# Arduino_MEGA_2560-Rev3.net
KiCad netlist of a schematic drawn in EAGLE
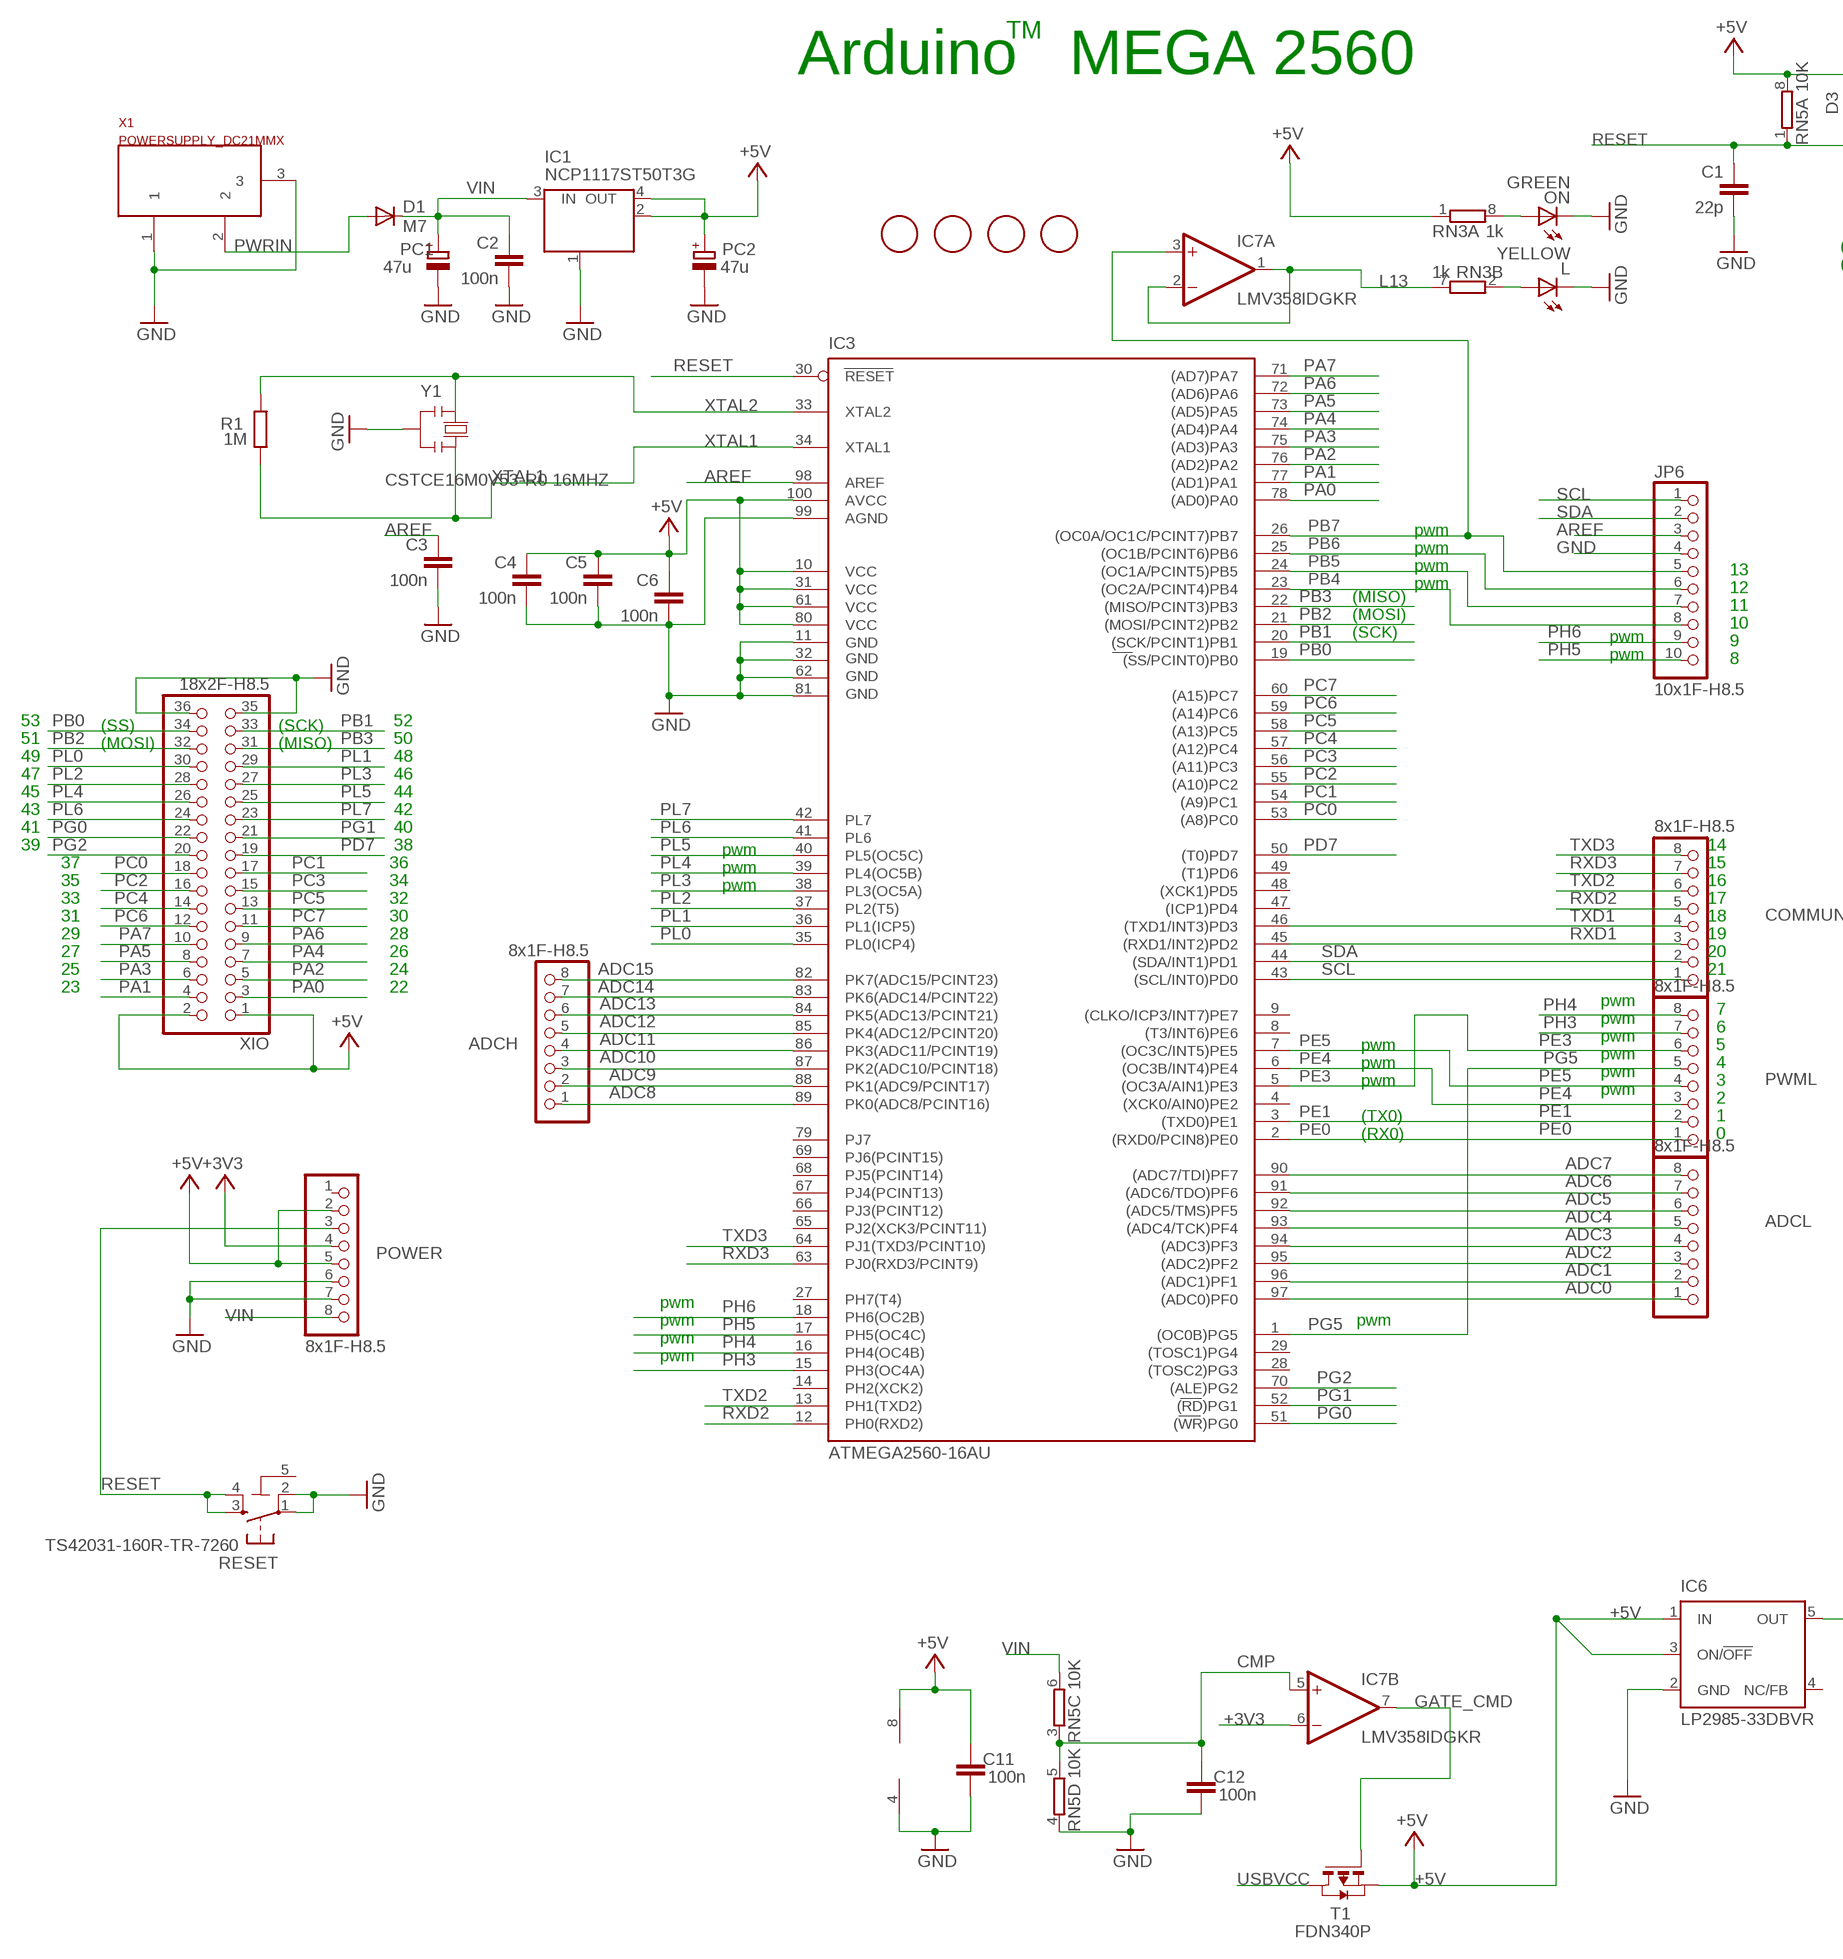
[diagram p0: schematic, sheet 1, part 1 of 2]
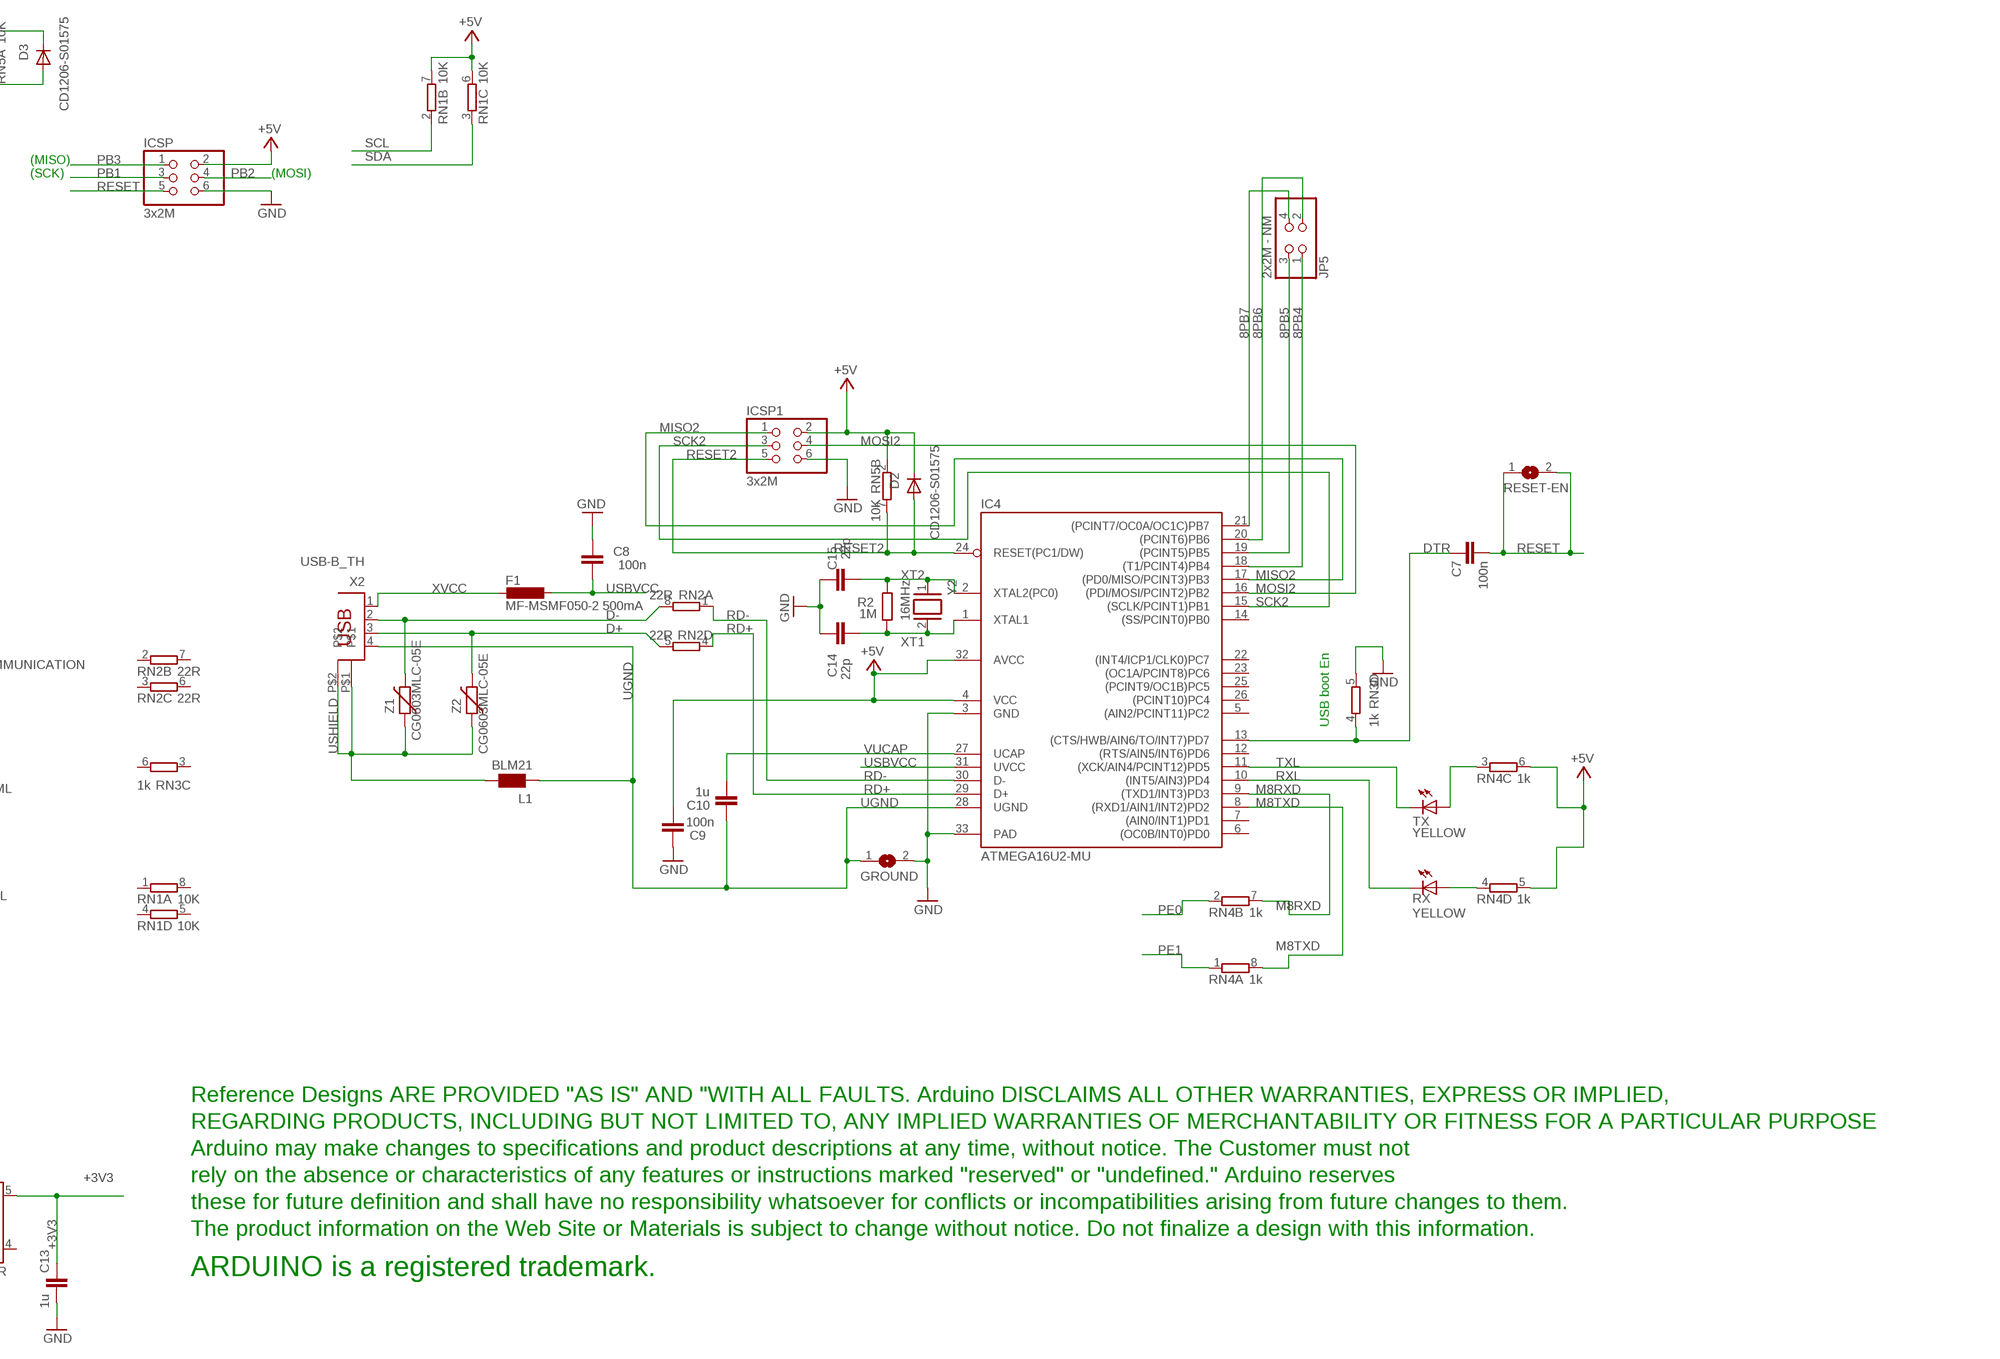
[diagram p1: schematic, sheet 1, part 2 of 2]

(export (version "E")
  (design (tool "Eeschema 10.0.6"))
  (components
    (comp (ref "ADCH")
      (value "8x1F-H8.5")
      (footprint "eagle-import:1X08")
      (libsource (lib "eagle-import") (part "PINHD-1X8"))
    )
    (comp (ref "ADCL")
      (value "8x1F-H8.5")
      (footprint "eagle-import:1X08")
      (libsource (lib "eagle-import") (part "PINHD-1X8"))
    )
    (comp (ref "C1")
      (value "22p")
      (footprint "eagle-import:C0603-ROUND")
      (libsource (lib "eagle-import") (part "C-EU0603-RND"))
    )
    (comp (ref "C2")
      (value "100n")
      (footprint "eagle-import:C0603-ROUND")
      (libsource (lib "eagle-import") (part "C-EU0603-RND"))
    )
    (comp (ref "C3")
      (value "100n")
      (footprint "eagle-import:C0603-ROUND")
      (libsource (lib "eagle-import") (part "C-EU0603-RND"))
    )
    (comp (ref "C4")
      (value "100n")
      (footprint "eagle-import:C0603-ROUND")
      (libsource (lib "eagle-import") (part "C-EU0603-RND"))
    )
    (comp (ref "C5")
      (value "100n")
      (footprint "eagle-import:C0603-ROUND")
      (libsource (lib "eagle-import") (part "C-EU0603-RND"))
    )
    (comp (ref "C6")
      (value "100n")
      (footprint "eagle-import:C0603-ROUND")
      (libsource (lib "eagle-import") (part "C-EU0603-RND"))
    )
    (comp (ref "C7")
      (value "100n")
      (footprint "eagle-import:C0603-ROUND")
      (libsource (lib "eagle-import") (part "C-EU0603-RND"))
    )
    (comp (ref "C8")
      (value "100n")
      (footprint "eagle-import:C0603-ROUND")
      (libsource (lib "eagle-import") (part "C-EU0603-RND"))
    )
    (comp (ref "C9")
      (value "100n")
      (footprint "eagle-import:C0603-ROUND")
      (libsource (lib "eagle-import") (part "C-EU0603-RND"))
    )
    (comp (ref "C10")
      (value "1u")
      (footprint "eagle-import:C0603-ROUND")
      (libsource (lib "eagle-import") (part "C-EU0603-RND"))
    )
    (comp (ref "C11")
      (value "100n")
      (footprint "eagle-import:C0603-ROUND")
      (libsource (lib "eagle-import") (part "C-EU0603-RND"))
    )
    (comp (ref "C12")
      (value "100n")
      (footprint "eagle-import:C0603-ROUND")
      (libsource (lib "eagle-import") (part "C-EU0603-RND"))
    )
    (comp (ref "C13")
      (value "1u")
      (footprint "eagle-import:C0603-ROUND")
      (libsource (lib "eagle-import") (part "C-EU0603-RND"))
    )
    (comp (ref "C14")
      (value "22p")
      (footprint "eagle-import:C0603-ROUND")
      (libsource (lib "eagle-import") (part "C-EU0603-RND"))
    )
    (comp (ref "C15")
      (value "22p")
      (footprint "eagle-import:C0603-ROUND")
      (libsource (lib "eagle-import") (part "C-EU0603-RND"))
    )
    (comp (ref "COMMUNICATION")
      (value "8x1F-H8.5")
      (footprint "eagle-import:1X08")
      (libsource (lib "eagle-import") (part "PINHD-1X8"))
    )
    (comp (ref "D1")
      (value "M7")
      (footprint "eagle-import:SMB")
      (libsource (lib "eagle-import") (part "DIODE-SMB"))
    )
    (comp (ref "D2")
      (value "CD1206-S01575")
      (footprint "eagle-import:MINIMELF")
      (libsource (lib "eagle-import") (part "DIODE-MINIMELF"))
    )
    (comp (ref "D3")
      (value "CD1206-S01575")
      (footprint "eagle-import:MINIMELF")
      (libsource (lib "eagle-import") (part "DIODE-MINIMELF"))
    )
    (comp (ref "F1")
      (value "MF-MSMF050-2 500mA")
      (footprint "eagle-import:L1812")
      (libsource (lib "eagle-import") (part "L-EUL1812"))
    )
    (comp (ref "FD1")
      (value "FIDUCIALMOUNT")
      (footprint "eagle-import:FIDUCIA-MOUNT")
      (libsource (lib "eagle-import") (part "FIDUCIALMOUNT"))
    )
    (comp (ref "FD2")
      (value "FIDUCIALMOUNT")
      (footprint "eagle-import:FIDUCIA-MOUNT")
      (libsource (lib "eagle-import") (part "FIDUCIALMOUNT"))
    )
    (comp (ref "FD3")
      (value "FIDUCIALMOUNT")
      (footprint "eagle-import:FIDUCIA-MOUNT")
      (libsource (lib "eagle-import") (part "FIDUCIALMOUNT"))
    )
    (comp (ref "FD4")
      (value "FIDUCIALMOUNT")
      (footprint "eagle-import:FIDUCIA-MOUNT")
      (libsource (lib "eagle-import") (part "FIDUCIALMOUNT"))
    )
    (comp (ref "GROUND")
      (value "SJ")
      (footprint "eagle-import:SJ")
      (libsource (lib "eagle-import") (part "SJ"))
    )
    (comp (ref "IC1")
      (value "NCP1117ST50T3G")
      (footprint "eagle-import:SOT223")
      (libsource (lib "eagle-import") (part "MC33269ST-3.3T3"))
    )
    (comp (ref "IC3")
      (value "ATMEGA2560-16AU")
      (footprint "eagle-import:TQFP100")
      (libsource (lib "eagle-import") (part "ATMEGA2560AU2560-16"))
    )
    (comp (ref "IC4")
      (value "ATMEGA16U2-MU")
      (footprint "eagle-import:MLF32")
      (libsource (lib "eagle-import") (part "ATMEGA16U2-MU"))
    )
    (comp (ref "IC6")
      (value "LP2985-33DBVR")
      (footprint "eagle-import:SOT23-DBV")
      (libsource (lib "eagle-import") (part "LP2985-XXDBVR33"))
    )
    (comp (ref "IC7")
      (value "LMV358IDGKR")
      (footprint "eagle-import:MSOP08")
      (libsource (lib "eagle-import") (part "LMV358?MMX"))
    )
    (comp (ref "ICSP")
      (value "3x2M")
      (footprint "eagle-import:2X03")
      (libsource (lib "eagle-import") (part "PINHD-2X3"))
    )
    (comp (ref "ICSP1")
      (value "3x2M")
      (footprint "eagle-import:2X03")
      (libsource (lib "eagle-import") (part "PINHD-2X3"))
    )
    (comp (ref "JP5")
      (value "2x2M - NM")
      (footprint "eagle-import:2X02")
      (libsource (lib "eagle-import") (part "PINHD-2X2"))
    )
    (comp (ref "JP6")
      (value "10x1F-H8.5")
      (footprint "eagle-import:1X10")
      (libsource (lib "eagle-import") (part "PINHD-1X10_ARD"))
    )
    (comp (ref "L")
      (value "YELLOW")
      (footprint "eagle-import:CHIP-LED0805")
      (libsource (lib "eagle-import") (part "LEDCHIP-LED0805"))
    )
    (comp (ref "L1")
      (value "BLM21")
      (footprint "eagle-import:0805")
      (libsource (lib "eagle-import") (part "WE-CBF_0805"))
    )
    (comp (ref "ON")
      (value "GREEN")
      (footprint "eagle-import:CHIP-LED0805")
      (libsource (lib "eagle-import") (part "LEDCHIP-LED0805"))
    )
    (comp (ref "PC1")
      (value "47u")
      (footprint "eagle-import:PANASONIC_D")
      (libsource (lib "eagle-import") (part "CPOL-EUD"))
    )
    (comp (ref "PC2")
      (value "47u")
      (footprint "eagle-import:PANASONIC_D")
      (libsource (lib "eagle-import") (part "CPOL-EUD"))
    )
    (comp (ref "POWER")
      (value "8x1F-H8.5")
      (footprint "eagle-import:1X08")
      (libsource (lib "eagle-import") (part "PINHD-1X8"))
    )
    (comp (ref "PWML")
      (value "8x1F-H8.5")
      (footprint "eagle-import:1X08")
      (libsource (lib "eagle-import") (part "PINHD-1X8"))
    )
    (comp (ref "R1")
      (value "1M")
      (footprint "eagle-import:R0603-ROUND")
      (libsource (lib "eagle-import") (part "R-EU_R0603"))
    )
    (comp (ref "R2")
      (value "1M")
      (footprint "eagle-import:R0603-ROUND")
      (libsource (lib "eagle-import") (part "R-EU_R0603"))
    )
    (comp (ref "RESET")
      (value "TS42031-160R-TR-7260")
      (footprint "eagle-import:TS42")
      (libsource (lib "eagle-import") (part "TS42"))
    )
    (comp (ref "RESET-EN")
      (value "SJ")
      (footprint "eagle-import:SJ")
      (libsource (lib "eagle-import") (part "SJ"))
    )
    (comp (ref "RN1")
      (value "10K")
      (footprint "eagle-import:CAT16")
      (libsource (lib "eagle-import") (part "4R-NCAT16"))
    )
    (comp (ref "RN2")
      (value "22R")
      (footprint "eagle-import:CAY16")
      (libsource (lib "eagle-import") (part "4R-NCAY16"))
    )
    (comp (ref "RN3")
      (value "1k")
      (footprint "eagle-import:CAY16")
      (libsource (lib "eagle-import") (part "4R-NCAY16"))
    )
    (comp (ref "RN4")
      (value "1k")
      (footprint "eagle-import:CAY16")
      (libsource (lib "eagle-import") (part "4R-NCAY16"))
    )
    (comp (ref "RN5")
      (value "10K")
      (footprint "eagle-import:CAT16")
      (libsource (lib "eagle-import") (part "4R-NCAT16"))
    )
    (comp (ref "RX")
      (value "YELLOW")
      (footprint "eagle-import:CHIP-LED0805")
      (libsource (lib "eagle-import") (part "LEDCHIP-LED0805"))
    )
    (comp (ref "T1")
      (value "FDN340P")
      (footprint "eagle-import:SOT-23")
      (libsource (lib "eagle-import") (part "PMOSSOT23"))
    )
    (comp (ref "TX")
      (value "YELLOW")
      (footprint "eagle-import:CHIP-LED0805")
      (libsource (lib "eagle-import") (part "LEDCHIP-LED0805"))
    )
    (comp (ref "U$1")
      (value "DISCLAIMER")
      (footprint "eagle-import:DISCLAIMER")
      (libsource (lib "eagle-import") (part "DISCLAIMER"))
    )
    (comp (ref "X1")
      (value "POWERSUPPLY_DC21MMX")
      (footprint "eagle-import:POWERSUPPLY_DC-21MM")
      (libsource (lib "eagle-import") (part "POWERSUPPLY_DC21MMX"))
    )
    (comp (ref "X2")
      (value "USB-B_TH")
      (footprint "eagle-import:PN61729")
      (libsource (lib "eagle-import") (part "PN61729"))
    )
    (comp (ref "XIO")
      (value "18x2F-H8.5")
      (footprint "eagle-import:2X18")
      (libsource (lib "eagle-import") (part "PINHD-2X18"))
    )
    (comp (ref "Y1")
      (value "CSTCE16M0V53-R0 16MHZ")
      (footprint "eagle-import:RESONATOR")
      (libsource (lib "eagle-import") (part "RESONATORMU"))
    )
    (comp (ref "Y2")
      (value "16MHz")
      (footprint "eagle-import:QS")
      (libsource (lib "eagle-import") (part "XTAL/S"))
    )
    (comp (ref "Z1")
      (value "CG0603MLC-05E")
      (footprint "eagle-import:CT_CN0603")
      (libsource (lib "eagle-import") (part "VARISTORCN0603"))
    )
    (comp (ref "Z2")
      (value "CG0603MLC-05E")
      (footprint "eagle-import:CT_CN0603")
      (libsource (lib "eagle-import") (part "VARISTORCN0603"))
    )
  )
  (nets
    (net (code "1") (name "+3V3") (class "Default")
      (node (ref "C13") (pin "2") (pinfunction "2_2") (pintype "passive"))
      (node (ref "IC6") (pin "5") (pinfunction "OUT_5") (pintype "passive"))
      (node (ref "IC7") (pin "6") (pinfunction "-IN_6") (pintype "input"))
      (node (ref "POWER") (pin "4") (pinfunction "4_4") (pintype "passive"))
    )
    (net (code "2") (name "+5V") (class "Default")
      (node (ref "C11") (pin "2") (pinfunction "2_2") (pintype "passive"))
      (node (ref "C4") (pin "1") (pinfunction "1_1") (pintype "passive"))
      (node (ref "C5") (pin "1") (pinfunction "1_1") (pintype "passive"))
      (node (ref "C6") (pin "1") (pinfunction "1_1") (pintype "passive"))
      (node (ref "C9") (pin "1") (pinfunction "1_1") (pintype "passive"))
      (node (ref "D2") (pin "C") (pinfunction "C_C") (pintype "passive"))
      (node (ref "D3") (pin "C") (pinfunction "C_C") (pintype "passive"))
      (node (ref "IC1") (pin "2") (pinfunction "OUT_2") (pintype "passive"))
      (node (ref "IC1") (pin "4") (pinfunction "OUT_4") (pintype "passive"))
      (node (ref "IC3") (pin "10") (pinfunction "VCC_10") (pintype "power_in"))
      (node (ref "IC3") (pin "100") (pinfunction "AVCC_100") (pintype "power_in"))
      (node (ref "IC3") (pin "31") (pinfunction "VCC1_31") (pintype "power_in"))
      (node (ref "IC3") (pin "61") (pinfunction "VCC2_61") (pintype "power_in"))
      (node (ref "IC3") (pin "80") (pinfunction "VCC3_80") (pintype "power_in"))
      (node (ref "IC4") (pin "32") (pinfunction "AVCC_32") (pintype "power_in"))
      (node (ref "IC4") (pin "4") (pinfunction "VCC_4") (pintype "power_in"))
      (node (ref "IC6") (pin "1") (pinfunction "IN_1") (pintype "input"))
      (node (ref "IC6") (pin "3") (pinfunction "ON/~{OFF}_3") (pintype "input"))
      (node (ref "IC7") (pin "8") (pinfunction "V+_8") (pintype "power_in"))
      (node (ref "ICSP") (pin "2") (pinfunction "2_2") (pintype "passive"))
      (node (ref "ICSP1") (pin "2") (pinfunction "2_2") (pintype "passive"))
      (node (ref "PC2") (pin "+") (pinfunction "+_+") (pintype "passive"))
      (node (ref "POWER") (pin "2") (pinfunction "2_2") (pintype "passive"))
      (node (ref "POWER") (pin "5") (pinfunction "5_5") (pintype "passive"))
      (node (ref "RN1") (pin "6") (pinfunction "2_6") (pintype "passive"))
      (node (ref "RN1") (pin "7") (pinfunction "2_7") (pintype "passive"))
      (node (ref "RN3") (pin "1") (pinfunction "1_1") (pintype "passive"))
      (node (ref "RN4") (pin "5") (pinfunction "2_5") (pintype "passive"))
      (node (ref "RN4") (pin "6") (pinfunction "2_6") (pintype "passive"))
      (node (ref "RN5") (pin "2") (pinfunction "1_2") (pintype "passive"))
      (node (ref "RN5") (pin "8") (pinfunction "2_8") (pintype "passive"))
      (node (ref "T1") (pin "2") (pinfunction "S_2") (pintype "passive"))
      (node (ref "XIO") (pin "1") (pinfunction "1_1") (pintype "passive"))
      (node (ref "XIO") (pin "2") (pinfunction "2_2") (pintype "passive"))
    )
    (net (code "3") (name "/5-GND") (class "Default")
      (node (ref "RESET") (pin "5") (pinfunction "5-GND_5") (pintype "power_in"))
    )
    (net (code "4") (name "/8PB4") (class "Default")
      (node (ref "IC4") (pin "18") (pinfunction "(T1/PCINT4)PB4_18") (pintype "bidirectional"))
      (node (ref "JP5") (pin "1") (pinfunction "1_1") (pintype "passive"))
    )
    (net (code "5") (name "/8PB5") (class "Default")
      (node (ref "IC4") (pin "19") (pinfunction "(PCINT5)PB5_19") (pintype "bidirectional"))
      (node (ref "JP5") (pin "3") (pinfunction "3_3") (pintype "passive"))
    )
    (net (code "6") (name "/8PB6") (class "Default")
      (node (ref "IC4") (pin "20") (pinfunction "(PCINT6)PB6_20") (pintype "bidirectional"))
      (node (ref "JP5") (pin "2") (pinfunction "2_2") (pintype "passive"))
    )
    (net (code "7") (name "/8PB7") (class "Default")
      (node (ref "IC4") (pin "21") (pinfunction "(PCINT7/OC0A/OC1C)PB7_21") (pintype "bidirectional"))
      (node (ref "JP5") (pin "4") (pinfunction "4_4") (pintype "passive"))
    )
    (net (code "8") (name "/ADC0") (class "Default")
      (node (ref "ADCL") (pin "1") (pinfunction "1_1") (pintype "passive"))
      (node (ref "IC3") (pin "97") (pinfunction "(ADC0)PF0_97") (pintype "bidirectional"))
    )
    (net (code "9") (name "/ADC1") (class "Default")
      (node (ref "ADCL") (pin "2") (pinfunction "2_2") (pintype "passive"))
      (node (ref "IC3") (pin "96") (pinfunction "(ADC1)PF1_96") (pintype "bidirectional"))
    )
    (net (code "10") (name "/ADC2") (class "Default")
      (node (ref "ADCL") (pin "3") (pinfunction "3_3") (pintype "passive"))
      (node (ref "IC3") (pin "95") (pinfunction "(ADC2)PF2_95") (pintype "bidirectional"))
    )
    (net (code "11") (name "/ADC3") (class "Default")
      (node (ref "ADCL") (pin "4") (pinfunction "4_4") (pintype "passive"))
      (node (ref "IC3") (pin "94") (pinfunction "(ADC3)PF3_94") (pintype "bidirectional"))
    )
    (net (code "12") (name "/ADC4") (class "Default")
      (node (ref "ADCL") (pin "5") (pinfunction "5_5") (pintype "passive"))
      (node (ref "IC3") (pin "93") (pinfunction "(ADC4/TCK)PF4_93") (pintype "bidirectional"))
    )
    (net (code "13") (name "/ADC5") (class "Default")
      (node (ref "ADCL") (pin "6") (pinfunction "6_6") (pintype "passive"))
      (node (ref "IC3") (pin "92") (pinfunction "(ADC5/TMS)PF5_92") (pintype "bidirectional"))
    )
    (net (code "14") (name "/ADC6") (class "Default")
      (node (ref "ADCL") (pin "7") (pinfunction "7_7") (pintype "passive"))
      (node (ref "IC3") (pin "91") (pinfunction "(ADC6/TDO)PF6_91") (pintype "bidirectional"))
    )
    (net (code "15") (name "/ADC7") (class "Default")
      (node (ref "ADCL") (pin "8") (pinfunction "8_8") (pintype "passive"))
      (node (ref "IC3") (pin "90") (pinfunction "(ADC7/TDI)PF7_90") (pintype "bidirectional"))
    )
    (net (code "16") (name "/ADC8") (class "Default")
      (node (ref "ADCH") (pin "1") (pinfunction "1_1") (pintype "passive"))
      (node (ref "IC3") (pin "89") (pinfunction "PK0(ADC8/PCINT16)_89") (pintype "bidirectional"))
    )
    (net (code "17") (name "/ADC9") (class "Default")
      (node (ref "ADCH") (pin "2") (pinfunction "2_2") (pintype "passive"))
      (node (ref "IC3") (pin "88") (pinfunction "PK1(ADC9/PCINT17)_88") (pintype "bidirectional"))
    )
    (net (code "18") (name "/ADC10") (class "Default")
      (node (ref "ADCH") (pin "3") (pinfunction "3_3") (pintype "passive"))
      (node (ref "IC3") (pin "87") (pinfunction "PK2(ADC10/PCINT18)_87") (pintype "bidirectional"))
    )
    (net (code "19") (name "/ADC11") (class "Default")
      (node (ref "ADCH") (pin "4") (pinfunction "4_4") (pintype "passive"))
      (node (ref "IC3") (pin "86") (pinfunction "PK3(ADC11/PCINT19)_86") (pintype "bidirectional"))
    )
    (net (code "20") (name "/ADC12") (class "Default")
      (node (ref "ADCH") (pin "5") (pinfunction "5_5") (pintype "passive"))
      (node (ref "IC3") (pin "85") (pinfunction "PK4(ADC12/PCINT20)_85") (pintype "bidirectional"))
    )
    (net (code "21") (name "/ADC13") (class "Default")
      (node (ref "ADCH") (pin "6") (pinfunction "6_6") (pintype "passive"))
      (node (ref "IC3") (pin "84") (pinfunction "PK5(ADC13/PCINT21)_84") (pintype "bidirectional"))
    )
    (net (code "22") (name "/ADC14") (class "Default")
      (node (ref "ADCH") (pin "7") (pinfunction "7_7") (pintype "passive"))
      (node (ref "IC3") (pin "83") (pinfunction "PK6(ADC14/PCINT22)_83") (pintype "bidirectional"))
    )
    (net (code "23") (name "/ADC15") (class "Default")
      (node (ref "ADCH") (pin "8") (pinfunction "8_8") (pintype "passive"))
      (node (ref "IC3") (pin "82") (pinfunction "PK7(ADC15/PCINT23)_82") (pintype "bidirectional"))
    )
    (net (code "24") (name "/AREF") (class "Default")
      (node (ref "C3") (pin "1") (pinfunction "1_1") (pintype "passive"))
      (node (ref "IC3") (pin "98") (pinfunction "AREF_98") (pintype "bidirectional"))
      (node (ref "JP6") (pin "3") (pinfunction "3_3") (pintype "passive"))
    )
    (net (code "25") (name "/CMP") (class "Default")
      (node (ref "C12") (pin "2") (pinfunction "2_2") (pintype "passive"))
      (node (ref "IC7") (pin "5") (pinfunction "+IN_5") (pintype "input"))
      (node (ref "RN5") (pin "3") (pinfunction "1_3") (pintype "passive"))
      (node (ref "RN5") (pin "5") (pinfunction "2_5") (pintype "passive"))
    )
    (net (code "26") (name "/D+") (class "Default")
      (node (ref "RN2") (pin "5") (pinfunction "2_5") (pintype "passive"))
      (node (ref "X2") (pin "3") (pinfunction "3_3") (pintype "bidirectional"))
      (node (ref "Z2") (pin "2") (pinfunction "2_2") (pintype "passive"))
    )
    (net (code "27") (name "/D-") (class "Default")
      (node (ref "RN2") (pin "8") (pinfunction "2_8") (pintype "passive"))
      (node (ref "X2") (pin "2") (pinfunction "2_2") (pintype "bidirectional"))
      (node (ref "Z1") (pin "2") (pinfunction "2_2") (pintype "passive"))
    )
    (net (code "28") (name "/DTR") (class "Default")
      (node (ref "C7") (pin "1") (pinfunction "1_1") (pintype "passive"))
      (node (ref "IC4") (pin "13") (pinfunction "(CTS/HWB/AIN6/TO/INT7)PD7_13") (pintype "bidirectional"))
      (node (ref "RN3") (pin "4") (pinfunction "1_4") (pintype "passive"))
    )
    (net (code "29") (name "/GATE_CMD") (class "Default")
      (node (ref "IC7") (pin "7") (pinfunction "OUT_7") (pintype "output"))
      (node (ref "T1") (pin "3") (pinfunction "G_3") (pintype "passive"))
    )
    (net (code "30") (name "/L13") (class "Default")
      (node (ref "IC7") (pin "1") (pinfunction "OUT_1") (pintype "output"))
      (node (ref "IC7") (pin "2") (pinfunction "-IN_2") (pintype "input"))
      (node (ref "RN3") (pin "7") (pinfunction "2_7") (pintype "passive"))
    )
    (net (code "31") (name "/M8RXD") (class "Default")
      (node (ref "IC4") (pin "9") (pinfunction "(TXD1/INT3)PD3_9") (pintype "bidirectional"))
      (node (ref "RN4") (pin "7") (pinfunction "2_7") (pintype "passive"))
    )
    (net (code "32") (name "/M8TXD") (class "Default")
      (node (ref "IC4") (pin "8") (pinfunction "(RXD1/AIN1/INT2)PD2_8") (pintype "bidirectional"))
      (node (ref "RN4") (pin "8") (pinfunction "2_8") (pintype "passive"))
    )
    (net (code "33") (name "/MISO2") (class "Default")
      (node (ref "IC4") (pin "17") (pinfunction "(PD0/MISO/PCINT3)PB3_17") (pintype "bidirectional"))
      (node (ref "ICSP1") (pin "1") (pinfunction "1_1") (pintype "passive"))
    )
    (net (code "34") (name "/MOSI2") (class "Default")
      (node (ref "IC4") (pin "16") (pinfunction "(PDI/MOSI/PCINT2)PB2_16") (pintype "bidirectional"))
      (node (ref "ICSP1") (pin "4") (pinfunction "4_4") (pintype "passive"))
    )
    (net (code "35") (name "/PA0") (class "Default")
      (node (ref "IC3") (pin "78") (pinfunction "(AD0)PA0_78") (pintype "bidirectional"))
      (node (ref "XIO") (pin "3") (pinfunction "3_3") (pintype "passive"))
    )
    (net (code "36") (name "/PA1") (class "Default")
      (node (ref "IC3") (pin "77") (pinfunction "(AD1)PA1_77") (pintype "bidirectional"))
      (node (ref "XIO") (pin "4") (pinfunction "4_4") (pintype "passive"))
    )
    (net (code "37") (name "/PA2") (class "Default")
      (node (ref "IC3") (pin "76") (pinfunction "(AD2)PA2_76") (pintype "bidirectional"))
      (node (ref "XIO") (pin "5") (pinfunction "5_5") (pintype "passive"))
    )
    (net (code "38") (name "/PA3") (class "Default")
      (node (ref "IC3") (pin "75") (pinfunction "(AD3)PA3_75") (pintype "bidirectional"))
      (node (ref "XIO") (pin "6") (pinfunction "6_6") (pintype "passive"))
    )
    (net (code "39") (name "/PA4") (class "Default")
      (node (ref "IC3") (pin "74") (pinfunction "(AD4)PA4_74") (pintype "bidirectional"))
      (node (ref "XIO") (pin "7") (pinfunction "7_7") (pintype "passive"))
    )
    (net (code "40") (name "/PA5") (class "Default")
      (node (ref "IC3") (pin "73") (pinfunction "(AD5)PA5_73") (pintype "bidirectional"))
      (node (ref "XIO") (pin "8") (pinfunction "8_8") (pintype "passive"))
    )
    (net (code "41") (name "/PA6") (class "Default")
      (node (ref "IC3") (pin "72") (pinfunction "(AD6)PA6_72") (pintype "bidirectional"))
      (node (ref "XIO") (pin "9") (pinfunction "9_9") (pintype "passive"))
    )
    (net (code "42") (name "/PA7") (class "Default")
      (node (ref "IC3") (pin "71") (pinfunction "(AD7)PA7_71") (pintype "bidirectional"))
      (node (ref "XIO") (pin "10") (pinfunction "10_10") (pintype "passive"))
    )
    (net (code "43") (name "/PB0") (class "Default")
      (node (ref "IC3") (pin "19") (pinfunction "(SS/PCINT0)PB0_19") (pintype "bidirectional"))
      (node (ref "XIO") (pin "34") (pinfunction "34_34") (pintype "passive"))
    )
    (net (code "44") (name "/PB1") (class "Default")
      (node (ref "IC3") (pin "20") (pinfunction "(SCK/PCINT1)PB1_20") (pintype "bidirectional"))
      (node (ref "ICSP") (pin "3") (pinfunction "3_3") (pintype "passive"))
      (node (ref "XIO") (pin "33") (pinfunction "33_33") (pintype "passive"))
    )
    (net (code "45") (name "/PB2") (class "Default")
      (node (ref "IC3") (pin "21") (pinfunction "(MOSI/PCINT2)PB2_21") (pintype "bidirectional"))
      (node (ref "ICSP") (pin "4") (pinfunction "4_4") (pintype "passive"))
      (node (ref "XIO") (pin "32") (pinfunction "32_32") (pintype "passive"))
    )
    (net (code "46") (name "/PB3") (class "Default")
      (node (ref "IC3") (pin "22") (pinfunction "(MISO/PCINT3)PB3_22") (pintype "bidirectional"))
      (node (ref "ICSP") (pin "1") (pinfunction "1_1") (pintype "passive"))
      (node (ref "XIO") (pin "31") (pinfunction "31_31") (pintype "passive"))
    )
    (net (code "47") (name "/PB4") (class "Default")
      (node (ref "IC3") (pin "23") (pinfunction "(OC2A/PCINT4)PB4_23") (pintype "bidirectional"))
      (node (ref "JP6") (pin "8") (pinfunction "8_8") (pintype "passive"))
    )
    (net (code "48") (name "/PB5") (class "Default")
      (node (ref "IC3") (pin "24") (pinfunction "(OC1A/PCINT5)PB5_24") (pintype "bidirectional"))
      (node (ref "JP6") (pin "7") (pinfunction "7_7") (pintype "passive"))
    )
    (net (code "49") (name "/PB6") (class "Default")
      (node (ref "IC3") (pin "25") (pinfunction "(OC1B/PCINT6)PB6_25") (pintype "bidirectional"))
      (node (ref "JP6") (pin "6") (pinfunction "6_6") (pintype "passive"))
    )
    (net (code "50") (name "/PB7") (class "Default")
      (node (ref "IC3") (pin "26") (pinfunction "(OC0A/OC1C/PCINT7)PB7_26") (pintype "bidirectional"))
      (node (ref "IC7") (pin "3") (pinfunction "+IN_3") (pintype "input"))
      (node (ref "JP6") (pin "5") (pinfunction "5_5") (pintype "passive"))
    )
    (net (code "51") (name "/PC0") (class "Default")
      (node (ref "IC3") (pin "53") (pinfunction "(A8)PC0_53") (pintype "bidirectional"))
      (node (ref "XIO") (pin "18") (pinfunction "18_18") (pintype "passive"))
    )
    (net (code "52") (name "/PC1") (class "Default")
      (node (ref "IC3") (pin "54") (pinfunction "(A9)PC1_54") (pintype "bidirectional"))
      (node (ref "XIO") (pin "17") (pinfunction "17_17") (pintype "passive"))
    )
    (net (code "53") (name "/PC2") (class "Default")
      (node (ref "IC3") (pin "55") (pinfunction "(A10)PC2_55") (pintype "bidirectional"))
      (node (ref "XIO") (pin "16") (pinfunction "16_16") (pintype "passive"))
    )
    (net (code "54") (name "/PC3") (class "Default")
      (node (ref "IC3") (pin "56") (pinfunction "(A11)PC3_56") (pintype "bidirectional"))
      (node (ref "XIO") (pin "15") (pinfunction "15_15") (pintype "passive"))
    )
    (net (code "55") (name "/PC4") (class "Default")
      (node (ref "IC3") (pin "57") (pinfunction "(A12)PC4_57") (pintype "bidirectional"))
      (node (ref "XIO") (pin "14") (pinfunction "14_14") (pintype "passive"))
    )
    (net (code "56") (name "/PC5") (class "Default")
      (node (ref "IC3") (pin "58") (pinfunction "(A13)PC5_58") (pintype "bidirectional"))
      (node (ref "XIO") (pin "13") (pinfunction "13_13") (pintype "passive"))
    )
    (net (code "57") (name "/PC6") (class "Default")
      (node (ref "IC3") (pin "59") (pinfunction "(A14)PC6_59") (pintype "bidirectional"))
      (node (ref "XIO") (pin "12") (pinfunction "12_12") (pintype "passive"))
    )
    (net (code "58") (name "/PC7") (class "Default")
      (node (ref "IC3") (pin "60") (pinfunction "(A15)PC7_60") (pintype "bidirectional"))
      (node (ref "XIO") (pin "11") (pinfunction "11_11") (pintype "passive"))
    )
    (net (code "59") (name "/PD7") (class "Default")
      (node (ref "IC3") (pin "50") (pinfunction "(T0)PD7_50") (pintype "bidirectional"))
      (node (ref "XIO") (pin "19") (pinfunction "19_19") (pintype "passive"))
    )
    (net (code "60") (name "/PE0") (class "Default")
      (node (ref "IC3") (pin "2") (pinfunction "(RXD0/PCIN8)PE0_2") (pintype "bidirectional"))
      (node (ref "PWML") (pin "1") (pinfunction "1_1") (pintype "passive"))
      (node (ref "RN4") (pin "2") (pinfunction "1_2") (pintype "passive"))
    )
    (net (code "61") (name "/PE1") (class "Default")
      (node (ref "IC3") (pin "3") (pinfunction "(TXD0)PE1_3") (pintype "bidirectional"))
      (node (ref "PWML") (pin "2") (pinfunction "2_2") (pintype "passive"))
      (node (ref "RN4") (pin "1") (pinfunction "1_1") (pintype "passive"))
    )
    (net (code "62") (name "/PE3") (class "Default")
      (node (ref "IC3") (pin "5") (pinfunction "(OC3A/AIN1)PE3_5") (pintype "bidirectional"))
      (node (ref "PWML") (pin "6") (pinfunction "6_6") (pintype "passive"))
    )
    (net (code "63") (name "/PE4") (class "Default")
      (node (ref "IC3") (pin "6") (pinfunction "(OC3B/INT4)PE4_6") (pintype "bidirectional"))
      (node (ref "PWML") (pin "3") (pinfunction "3_3") (pintype "passive"))
    )
    (net (code "64") (name "/PE5") (class "Default")
      (node (ref "IC3") (pin "7") (pinfunction "(OC3C/INT5)PE5_7") (pintype "bidirectional"))
      (node (ref "PWML") (pin "4") (pinfunction "4_4") (pintype "passive"))
    )
    (net (code "65") (name "/PG0") (class "Default")
      (node (ref "IC3") (pin "51") (pinfunction "(WR)PG0_51") (pintype "bidirectional"))
      (node (ref "XIO") (pin "22") (pinfunction "22_22") (pintype "passive"))
    )
    (net (code "66") (name "/PG1") (class "Default")
      (node (ref "IC3") (pin "52") (pinfunction "(RD)PG1_52") (pintype "bidirectional"))
      (node (ref "XIO") (pin "21") (pinfunction "21_21") (pintype "passive"))
    )
    (net (code "67") (name "/PG2") (class "Default")
      (node (ref "IC3") (pin "70") (pinfunction "(ALE)PG2_70") (pintype "bidirectional"))
      (node (ref "XIO") (pin "20") (pinfunction "20_20") (pintype "passive"))
    )
    (net (code "68") (name "/PG5") (class "Default")
      (node (ref "IC3") (pin "1") (pinfunction "(OC0B)PG5_1") (pintype "bidirectional"))
      (node (ref "PWML") (pin "5") (pinfunction "5_5") (pintype "passive"))
    )
    (net (code "69") (name "/PH3") (class "Default")
      (node (ref "IC3") (pin "15") (pinfunction "PH3(OC4A)_15") (pintype "bidirectional"))
      (node (ref "PWML") (pin "7") (pinfunction "7_7") (pintype "passive"))
    )
    (net (code "70") (name "/PH4") (class "Default")
      (node (ref "IC3") (pin "16") (pinfunction "PH4(OC4B)_16") (pintype "bidirectional"))
      (node (ref "PWML") (pin "8") (pinfunction "8_8") (pintype "passive"))
    )
    (net (code "71") (name "/PH5") (class "Default")
      (node (ref "IC3") (pin "17") (pinfunction "PH5(OC4C)_17") (pintype "bidirectional"))
      (node (ref "JP6") (pin "10") (pinfunction "10_10") (pintype "passive"))
    )
    (net (code "72") (name "/PH6") (class "Default")
      (node (ref "IC3") (pin "18") (pinfunction "PH6(OC2B)_18") (pintype "bidirectional"))
      (node (ref "JP6") (pin "9") (pinfunction "9_9") (pintype "passive"))
    )
    (net (code "73") (name "/PL0") (class "Default")
      (node (ref "IC3") (pin "35") (pinfunction "PL0(ICP4)_35") (pintype "bidirectional"))
      (node (ref "XIO") (pin "30") (pinfunction "30_30") (pintype "passive"))
    )
    (net (code "74") (name "/PL1") (class "Default")
      (node (ref "IC3") (pin "36") (pinfunction "PL1(ICP5)_36") (pintype "bidirectional"))
      (node (ref "XIO") (pin "29") (pinfunction "29_29") (pintype "passive"))
    )
    (net (code "75") (name "/PL2") (class "Default")
      (node (ref "IC3") (pin "37") (pinfunction "PL2(T5)_37") (pintype "bidirectional"))
      (node (ref "XIO") (pin "28") (pinfunction "28_28") (pintype "passive"))
    )
    (net (code "76") (name "/PL3") (class "Default")
      (node (ref "IC3") (pin "38") (pinfunction "PL3(OC5A)_38") (pintype "bidirectional"))
      (node (ref "XIO") (pin "27") (pinfunction "27_27") (pintype "passive"))
    )
    (net (code "77") (name "/PL4") (class "Default")
      (node (ref "IC3") (pin "39") (pinfunction "PL4(OC5B)_39") (pintype "bidirectional"))
      (node (ref "XIO") (pin "26") (pinfunction "26_26") (pintype "passive"))
    )
    (net (code "78") (name "/PL5") (class "Default")
      (node (ref "IC3") (pin "40") (pinfunction "PL5(OC5C)_40") (pintype "bidirectional"))
      (node (ref "XIO") (pin "25") (pinfunction "25_25") (pintype "passive"))
    )
    (net (code "79") (name "/PL6") (class "Default")
      (node (ref "IC3") (pin "41") (pinfunction "PL6_41") (pintype "bidirectional"))
      (node (ref "XIO") (pin "24") (pinfunction "24_24") (pintype "passive"))
    )
    (net (code "80") (name "/PL7") (class "Default")
      (node (ref "IC3") (pin "42") (pinfunction "PL7_42") (pintype "bidirectional"))
      (node (ref "XIO") (pin "23") (pinfunction "23_23") (pintype "passive"))
    )
    (net (code "81") (name "/PWRIN") (class "Default")
      (node (ref "D1") (pin "A") (pinfunction "A_A") (pintype "passive"))
      (node (ref "X1") (pin "2") (pinfunction "2_2") (pintype "power_in"))
    )
    (net (code "82") (name "/RD+") (class "Default")
      (node (ref "IC4") (pin "29") (pinfunction "D+_29") (pintype "bidirectional"))
      (node (ref "RN2") (pin "4") (pinfunction "1_4") (pintype "passive"))
    )
    (net (code "83") (name "/RD-") (class "Default")
      (node (ref "IC4") (pin "30") (pinfunction "D-_30") (pintype "bidirectional"))
      (node (ref "RN2") (pin "1") (pinfunction "1_1") (pintype "passive"))
    )
    (net (code "84") (name "/RESET") (class "Default")
      (node (ref "C1") (pin "1") (pinfunction "1_1") (pintype "passive"))
      (node (ref "C7") (pin "2") (pinfunction "2_2") (pintype "passive"))
      (node (ref "D3") (pin "A") (pinfunction "A_A") (pintype "passive"))
      (node (ref "IC3") (pin "30") (pinfunction "RESET_30") (pintype "input"))
      (node (ref "ICSP") (pin "5") (pinfunction "5_5") (pintype "passive"))
      (node (ref "POWER") (pin "3") (pinfunction "3_3") (pintype "passive"))
      (node (ref "RESET") (pin "3") (pinfunction "3_3") (pintype "passive"))
      (node (ref "RESET") (pin "4") (pinfunction "4_4") (pintype "passive"))
      (node (ref "RESET-EN") (pin "1") (pinfunction "1_1") (pintype "passive"))
      (node (ref "RESET-EN") (pin "2") (pinfunction "2_2") (pintype "passive"))
      (node (ref "RN5") (pin "1") (pinfunction "1_1") (pintype "passive"))
    )
    (net (code "85") (name "/RESET2") (class "Default")
      (node (ref "D2") (pin "A") (pinfunction "A_A") (pintype "passive"))
      (node (ref "IC4") (pin "24") (pinfunction "RESET(PC1/DW)_24") (pintype "input"))
      (node (ref "ICSP1") (pin "5") (pinfunction "5_5") (pintype "passive"))
      (node (ref "RN5") (pin "7") (pinfunction "2_7") (pintype "passive"))
    )
    (net (code "86") (name "/RXD1") (class "Default")
      (node (ref "COMMUNICATION") (pin "3") (pinfunction "3_3") (pintype "passive"))
      (node (ref "IC3") (pin "45") (pinfunction "(RXD1/INT2)PD2_45") (pintype "bidirectional"))
    )
    (net (code "87") (name "/RXD2") (class "Default")
      (node (ref "COMMUNICATION") (pin "5") (pinfunction "5_5") (pintype "passive"))
      (node (ref "IC3") (pin "12") (pinfunction "PH0(RXD2)_12") (pintype "bidirectional"))
    )
    (net (code "88") (name "/RXD3") (class "Default")
      (node (ref "COMMUNICATION") (pin "7") (pinfunction "7_7") (pintype "passive"))
      (node (ref "IC3") (pin "63") (pinfunction "PJ0(RXD3/PCINT9)_63") (pintype "bidirectional"))
    )
    (net (code "89") (name "/RXL") (class "Default")
      (node (ref "IC4") (pin "10") (pinfunction "(INT5/AIN3)PD4_10") (pintype "bidirectional"))
      (node (ref "RX") (pin "C") (pinfunction "C_C") (pintype "passive"))
    )
    (net (code "90") (name "/SCK2") (class "Default")
      (node (ref "IC4") (pin "15") (pinfunction "(SCLK/PCINT1)PB1_15") (pintype "bidirectional"))
      (node (ref "ICSP1") (pin "3") (pinfunction "3_3") (pintype "passive"))
    )
    (net (code "91") (name "/SCL") (class "Default")
      (node (ref "COMMUNICATION") (pin "1") (pinfunction "1_1") (pintype "passive"))
      (node (ref "IC3") (pin "43") (pinfunction "(SCL/INT0)PD0_43") (pintype "bidirectional"))
      (node (ref "JP6") (pin "1") (pinfunction "1_1") (pintype "passive"))
      (node (ref "RN1") (pin "2") (pinfunction "1_2") (pintype "passive"))
    )
    (net (code "92") (name "/SDA") (class "Default")
      (node (ref "COMMUNICATION") (pin "2") (pinfunction "2_2") (pintype "passive"))
      (node (ref "IC3") (pin "44") (pinfunction "(SDA/INT1)PD1_44") (pintype "bidirectional"))
      (node (ref "JP6") (pin "2") (pinfunction "2_2") (pintype "passive"))
      (node (ref "RN1") (pin "3") (pinfunction "1_3") (pintype "passive"))
    )
    (net (code "93") (name "/TXD1") (class "Default")
      (node (ref "COMMUNICATION") (pin "4") (pinfunction "4_4") (pintype "passive"))
      (node (ref "IC3") (pin "46") (pinfunction "(TXD1/INT3)PD3_46") (pintype "bidirectional"))
    )
    (net (code "94") (name "/TXD2") (class "Default")
      (node (ref "COMMUNICATION") (pin "6") (pinfunction "6_6") (pintype "passive"))
      (node (ref "IC3") (pin "13") (pinfunction "PH1(TXD2)_13") (pintype "bidirectional"))
    )
    (net (code "95") (name "/TXD3") (class "Default")
      (node (ref "COMMUNICATION") (pin "8") (pinfunction "8_8") (pintype "passive"))
      (node (ref "IC3") (pin "64") (pinfunction "PJ1(TXD3/PCINT10)_64") (pintype "bidirectional"))
    )
    (net (code "96") (name "/TXL") (class "Default")
      (node (ref "IC4") (pin "11") (pinfunction "(XCK/AIN4/PCINT12)PD5_11") (pintype "bidirectional"))
      (node (ref "TX") (pin "C") (pinfunction "C_C") (pintype "passive"))
    )
    (net (code "97") (name "/UGND") (class "Default")
      (node (ref "C10") (pin "2") (pinfunction "2_2") (pintype "passive"))
      (node (ref "GROUND") (pin "1") (pinfunction "1_1") (pintype "passive"))
      (node (ref "IC4") (pin "28") (pinfunction "UGND_28") (pintype "power_in"))
      (node (ref "L1") (pin "1") (pinfunction "1_1") (pintype "passive"))
      (node (ref "X2") (pin "4") (pinfunction "4_4") (pintype "bidirectional"))
    )
    (net (code "98") (name "/USBVCC") (class "Default")
      (node (ref "C8") (pin "1") (pinfunction "1_1") (pintype "passive"))
      (node (ref "F1") (pin "1") (pinfunction "1_1") (pintype "passive"))
      (node (ref "IC4") (pin "31") (pinfunction "UVCC_31") (pintype "power_in"))
      (node (ref "T1") (pin "1") (pinfunction "D_1") (pintype "passive"))
    )
    (net (code "99") (name "/USHIELD") (class "Default")
      (node (ref "L1") (pin "2") (pinfunction "2_2") (pintype "passive"))
      (node (ref "X2") (pin "P$1") (pinfunction "P$1_P$1") (pintype "bidirectional"))
      (node (ref "X2") (pin "P$2") (pinfunction "P$2_P$2") (pintype "bidirectional"))
      (node (ref "Z1") (pin "1") (pinfunction "1_1") (pintype "passive"))
      (node (ref "Z2") (pin "1") (pinfunction "1_1") (pintype "passive"))
    )
    (net (code "100") (name "/VIN") (class "Default")
      (node (ref "C2") (pin "1") (pinfunction "1_1") (pintype "passive"))
      (node (ref "D1") (pin "C") (pinfunction "C_C") (pintype "passive"))
      (node (ref "IC1") (pin "3") (pinfunction "IN_3") (pintype "input"))
      (node (ref "PC1") (pin "+") (pinfunction "+_+") (pintype "passive"))
      (node (ref "POWER") (pin "8") (pinfunction "8_8") (pintype "passive"))
      (node (ref "RN5") (pin "6") (pinfunction "2_6") (pintype "passive"))
    )
    (net (code "101") (name "/VUCAP") (class "Default")
      (node (ref "C10") (pin "1") (pinfunction "1_1") (pintype "passive"))
      (node (ref "IC4") (pin "27") (pinfunction "UCAP_27") (pintype "passive"))
    )
    (net (code "102") (name "/XT1") (class "Default")
      (node (ref "C14") (pin "1") (pinfunction "1_1") (pintype "passive"))
      (node (ref "IC4") (pin "1") (pinfunction "XTAL1_1") (pintype "bidirectional"))
      (node (ref "R2") (pin "1") (pinfunction "1_1") (pintype "passive"))
      (node (ref "Y2") (pin "2") (pinfunction "2_2") (pintype "passive"))
    )
    (net (code "103") (name "/XT2") (class "Default")
      (node (ref "C15") (pin "1") (pinfunction "1_1") (pintype "passive"))
      (node (ref "IC4") (pin "2") (pinfunction "XTAL2(PC0)_2") (pintype "bidirectional"))
      (node (ref "R2") (pin "2") (pinfunction "2_2") (pintype "passive"))
      (node (ref "Y2") (pin "1") (pinfunction "1_1") (pintype "passive"))
    )
    (net (code "104") (name "/XTAL1") (class "Default")
      (node (ref "IC3") (pin "34") (pinfunction "XTAL1_34") (pintype "input"))
      (node (ref "R1") (pin "1") (pinfunction "1_1") (pintype "passive"))
      (node (ref "Y1") (pin "3") (pinfunction "3_3") (pintype "passive"))
    )
    (net (code "105") (name "/XTAL2") (class "Default")
      (node (ref "IC3") (pin "33") (pinfunction "XTAL2_33") (pintype "output"))
      (node (ref "R1") (pin "2") (pinfunction "2_2") (pintype "passive"))
      (node (ref "Y1") (pin "1") (pinfunction "1_1") (pintype "passive"))
    )
    (net (code "106") (name "/XVCC") (class "Default")
      (node (ref "F1") (pin "2") (pinfunction "2_2") (pintype "passive"))
      (node (ref "X2") (pin "1") (pinfunction "1_1") (pintype "bidirectional"))
    )
    (net (code "107") (name "GND") (class "Default")
      (node (ref "C1") (pin "2") (pinfunction "2_2") (pintype "passive"))
      (node (ref "C11") (pin "1") (pinfunction "1_1") (pintype "passive"))
      (node (ref "C12") (pin "1") (pinfunction "1_1") (pintype "passive"))
      (node (ref "C13") (pin "1") (pinfunction "1_1") (pintype "passive"))
      (node (ref "C14") (pin "2") (pinfunction "2_2") (pintype "passive"))
      (node (ref "C15") (pin "2") (pinfunction "2_2") (pintype "passive"))
      (node (ref "C2") (pin "2") (pinfunction "2_2") (pintype "passive"))
      (node (ref "C3") (pin "2") (pinfunction "2_2") (pintype "passive"))
      (node (ref "C4") (pin "2") (pinfunction "2_2") (pintype "passive"))
      (node (ref "C5") (pin "2") (pinfunction "2_2") (pintype "passive"))
      (node (ref "C6") (pin "2") (pinfunction "2_2") (pintype "passive"))
      (node (ref "C8") (pin "2") (pinfunction "2_2") (pintype "passive"))
      (node (ref "C9") (pin "2") (pinfunction "2_2") (pintype "passive"))
      (node (ref "GROUND") (pin "2") (pinfunction "2_2") (pintype "passive"))
      (node (ref "IC1") (pin "1") (pinfunction "GND/ADJ_1") (pintype "input"))
      (node (ref "IC3") (pin "11") (pinfunction "GND_11") (pintype "power_in"))
      (node (ref "IC3") (pin "32") (pinfunction "GND1_32") (pintype "power_in"))
      (node (ref "IC3") (pin "62") (pinfunction "GND2_62") (pintype "power_in"))
      (node (ref "IC3") (pin "81") (pinfunction "GND3_81") (pintype "power_in"))
      (node (ref "IC3") (pin "99") (pinfunction "AGND_99") (pintype "power_in"))
      (node (ref "IC4") (pin "3") (pinfunction "GND_3") (pintype "power_in"))
      (node (ref "IC4") (pin "33") (pinfunction "PAD_33") (pintype "power_in"))
      (node (ref "IC6") (pin "2") (pinfunction "GND_2") (pintype "power_in"))
      (node (ref "IC7") (pin "4") (pinfunction "V-_4") (pintype "power_in"))
      (node (ref "ICSP") (pin "6") (pinfunction "6_6") (pintype "passive"))
      (node (ref "ICSP1") (pin "6") (pinfunction "6_6") (pintype "passive"))
      (node (ref "JP6") (pin "4") (pinfunction "4_4") (pintype "passive"))
      (node (ref "L") (pin "C") (pinfunction "C_C") (pintype "passive"))
      (node (ref "ON") (pin "C") (pinfunction "C_C") (pintype "passive"))
      (node (ref "PC1") (pin "-") (pinfunction "-_-") (pintype "passive"))
      (node (ref "PC2") (pin "-") (pinfunction "-_-") (pintype "passive"))
      (node (ref "POWER") (pin "6") (pinfunction "6_6") (pintype "passive"))
      (node (ref "POWER") (pin "7") (pinfunction "7_7") (pintype "passive"))
      (node (ref "RESET") (pin "1") (pinfunction "1_1") (pintype "passive"))
      (node (ref "RESET") (pin "2") (pinfunction "2_2") (pintype "passive"))
      (node (ref "RN3") (pin "5") (pinfunction "2_5") (pintype "passive"))
      (node (ref "RN5") (pin "4") (pinfunction "1_4") (pintype "passive"))
      (node (ref "X1") (pin "1") (pinfunction "1_1") (pintype "power_in"))
      (node (ref "X1") (pin "3") (pinfunction "3_3") (pintype "power_in"))
      (node (ref "XIO") (pin "35") (pinfunction "35_35") (pintype "passive"))
      (node (ref "XIO") (pin "36") (pinfunction "36_36") (pintype "passive"))
      (node (ref "Y1") (pin "2") (pinfunction "2_2") (pintype "passive"))
    )
    (net (code "108") (name "Net-(RN3A-2)") (class "Default")
      (node (ref "ON") (pin "A") (pinfunction "A_A") (pintype "passive"))
      (node (ref "RN3") (pin "8") (pinfunction "2_8") (pintype "passive"))
    )
    (net (code "109") (name "Net-(RN3B-1)") (class "Default")
      (node (ref "L") (pin "A") (pinfunction "A_A") (pintype "passive"))
      (node (ref "RN3") (pin "2") (pinfunction "1_2") (pintype "passive"))
    )
    (net (code "110") (name "Net-(RN4C-1)") (class "Default")
      (node (ref "RN4") (pin "3") (pinfunction "1_3") (pintype "passive"))
      (node (ref "TX") (pin "A") (pinfunction "A_A") (pintype "passive"))
    )
    (net (code "111") (name "Net-(RN4D-1)") (class "Default")
      (node (ref "RN4") (pin "4") (pinfunction "1_4") (pintype "passive"))
      (node (ref "RX") (pin "A") (pinfunction "A_A") (pintype "passive"))
    )
    (net (code "112") (name "unconnected-(IC3-(CLKO{slash}ICP3{slash}INT7)PE7-Pad9)") (class "Default")
      (node (ref "IC3") (pin "9") (pinfunction "(CLKO/ICP3/INT7)PE7_9") (pintype "bidirectional"))
    )
    (net (code "113") (name "unconnected-(IC3-(ICP1)PD4-Pad47)") (class "Default")
      (node (ref "IC3") (pin "47") (pinfunction "(ICP1)PD4_47") (pintype "bidirectional"))
    )
    (net (code "114") (name "unconnected-(IC3-(T1)PD6-Pad49)") (class "Default")
      (node (ref "IC3") (pin "49") (pinfunction "(T1)PD6_49") (pintype "bidirectional"))
    )
    (net (code "115") (name "unconnected-(IC3-(T3{slash}INT6)PE6-Pad8)") (class "Default")
      (node (ref "IC3") (pin "8") (pinfunction "(T3/INT6)PE6_8") (pintype "bidirectional"))
    )
    (net (code "116") (name "unconnected-(IC3-(TOSC1)PG4-Pad29)") (class "Default")
      (node (ref "IC3") (pin "29") (pinfunction "(TOSC1)PG4_29") (pintype "bidirectional"))
    )
    (net (code "117") (name "unconnected-(IC3-(TOSC2)PG3-Pad28)") (class "Default")
      (node (ref "IC3") (pin "28") (pinfunction "(TOSC2)PG3_28") (pintype "bidirectional"))
    )
    (net (code "118") (name "unconnected-(IC3-(XCK0{slash}AIN0)PE2-Pad4)") (class "Default")
      (node (ref "IC3") (pin "4") (pinfunction "(XCK0/AIN0)PE2_4") (pintype "bidirectional"))
    )
    (net (code "119") (name "unconnected-(IC3-(XCK1)PD5-Pad48)") (class "Default")
      (node (ref "IC3") (pin "48") (pinfunction "(XCK1)PD5_48") (pintype "bidirectional"))
    )
    (net (code "120") (name "unconnected-(IC3-PH2(XCK2)-Pad14)") (class "Default")
      (node (ref "IC3") (pin "14") (pinfunction "PH2(XCK2)_14") (pintype "bidirectional"))
    )
    (net (code "121") (name "unconnected-(IC3-PH7(T4)-Pad27)") (class "Default")
      (node (ref "IC3") (pin "27") (pinfunction "PH7(T4)_27") (pintype "bidirectional"))
    )
    (net (code "122") (name "unconnected-(IC3-PJ2(XCK3{slash}PCINT11)-Pad65)") (class "Default")
      (node (ref "IC3") (pin "65") (pinfunction "PJ2(XCK3/PCINT11)_65") (pintype "bidirectional"))
    )
    (net (code "123") (name "unconnected-(IC3-PJ3(PCINT12)-Pad66)") (class "Default")
      (node (ref "IC3") (pin "66") (pinfunction "PJ3(PCINT12)_66") (pintype "bidirectional"))
    )
    (net (code "124") (name "unconnected-(IC3-PJ4(PCINT13)-Pad67)") (class "Default")
      (node (ref "IC3") (pin "67") (pinfunction "PJ4(PCINT13)_67") (pintype "bidirectional"))
    )
    (net (code "125") (name "unconnected-(IC3-PJ5(PCINT14)-Pad68)") (class "Default")
      (node (ref "IC3") (pin "68") (pinfunction "PJ5(PCINT14)_68") (pintype "bidirectional"))
    )
    (net (code "126") (name "unconnected-(IC3-PJ6(PCINT15)-Pad69)") (class "Default")
      (node (ref "IC3") (pin "69") (pinfunction "PJ6(PCINT15)_69") (pintype "bidirectional"))
    )
    (net (code "127") (name "unconnected-(IC3-PJ7-Pad79)") (class "Default")
      (node (ref "IC3") (pin "79") (pinfunction "PJ7_79") (pintype "bidirectional"))
    )
    (net (code "128") (name "unconnected-(IC4-(AIN0{slash}INT1)PD1-Pad7)") (class "Default")
      (node (ref "IC4") (pin "7") (pinfunction "(AIN0/INT1)PD1_7") (pintype "bidirectional"))
    )
    (net (code "129") (name "unconnected-(IC4-(AIN2{slash}PCINT11)PC2-Pad5)") (class "Default")
      (node (ref "IC4") (pin "5") (pinfunction "(AIN2/PCINT11)PC2_5") (pintype "bidirectional"))
    )
    (net (code "130") (name "unconnected-(IC4-(INT4{slash}ICP1{slash}CLK0)PC7-Pad22)") (class "Default")
      (node (ref "IC4") (pin "22") (pinfunction "(INT4/ICP1/CLK0)PC7_22") (pintype "bidirectional"))
    )
    (net (code "131") (name "unconnected-(IC4-(OC0B{slash}INT0)PD0-Pad6)") (class "Default")
      (node (ref "IC4") (pin "6") (pinfunction "(OC0B/INT0)PD0_6") (pintype "bidirectional"))
    )
    (net (code "132") (name "unconnected-(IC4-(OC1A{slash}PCINT8)PC6-Pad23)") (class "Default")
      (node (ref "IC4") (pin "23") (pinfunction "(OC1A/PCINT8)PC6_23") (pintype "bidirectional"))
    )
    (net (code "133") (name "unconnected-(IC4-(PCINT9{slash}OC1B)PC5-Pad25)") (class "Default")
      (node (ref "IC4") (pin "25") (pinfunction "(PCINT9/OC1B)PC5_25") (pintype "bidirectional"))
    )
    (net (code "134") (name "unconnected-(IC4-(PCINT10)PC4-Pad26)") (class "Default")
      (node (ref "IC4") (pin "26") (pinfunction "(PCINT10)PC4_26") (pintype "bidirectional"))
    )
    (net (code "135") (name "unconnected-(IC4-(RTS{slash}AIN5{slash}INT6)PD6-Pad12)") (class "Default")
      (node (ref "IC4") (pin "12") (pinfunction "(RTS/AIN5/INT6)PD6_12") (pintype "bidirectional"))
    )
    (net (code "136") (name "unconnected-(IC4-(SS{slash}PCINT0)PB0-Pad14)") (class "Default")
      (node (ref "IC4") (pin "14") (pinfunction "(SS/PCINT0)PB0_14") (pintype "bidirectional"))
    )
    (net (code "137") (name "unconnected-(IC6-NC{slash}FB-Pad4)") (class "Default")
      (node (ref "IC6") (pin "4") (pinfunction "NC/FB_4") (pintype "passive"))
    )
    (net (code "138") (name "unconnected-(POWER-Pad1)") (class "Default")
      (node (ref "POWER") (pin "1") (pinfunction "1_1") (pintype "passive"))
    )
    (net (code "139") (name "unconnected-(RN1-Pad1)") (class "Default")
      (node (ref "RN1") (pin "1") (pinfunction "1_1") (pintype "passive"))
    )
    (net (code "140") (name "unconnected-(RN1A-2-Pad8)") (class "Default")
      (node (ref "RN1") (pin "8") (pinfunction "2_8") (pintype "passive"))
    )
    (net (code "141") (name "unconnected-(RN1D-1-Pad4)") (class "Default")
      (node (ref "RN1") (pin "4") (pinfunction "1_4") (pintype "passive"))
    )
    (net (code "142") (name "unconnected-(RN1D-2-Pad5)") (class "Default")
      (node (ref "RN1") (pin "5") (pinfunction "2_5") (pintype "passive"))
    )
    (net (code "143") (name "unconnected-(RN2B-1-Pad2)") (class "Default")
      (node (ref "RN2") (pin "2") (pinfunction "1_2") (pintype "passive"))
    )
    (net (code "144") (name "unconnected-(RN2B-2-Pad7)") (class "Default")
      (node (ref "RN2") (pin "7") (pinfunction "2_7") (pintype "passive"))
    )
    (net (code "145") (name "unconnected-(RN2C-1-Pad3)") (class "Default")
      (node (ref "RN2") (pin "3") (pinfunction "1_3") (pintype "passive"))
    )
    (net (code "146") (name "unconnected-(RN2C-2-Pad6)") (class "Default")
      (node (ref "RN2") (pin "6") (pinfunction "2_6") (pintype "passive"))
    )
    (net (code "147") (name "unconnected-(RN3C-1-Pad3)") (class "Default")
      (node (ref "RN3") (pin "3") (pinfunction "1_3") (pintype "passive"))
    )
    (net (code "148") (name "unconnected-(RN3C-2-Pad6)") (class "Default")
      (node (ref "RN3") (pin "6") (pinfunction "2_6") (pintype "passive"))
    )
  )
)
